# CEM-16bit-PCF8575.net
KiCad netlist of a schematic drawn in EAGLE
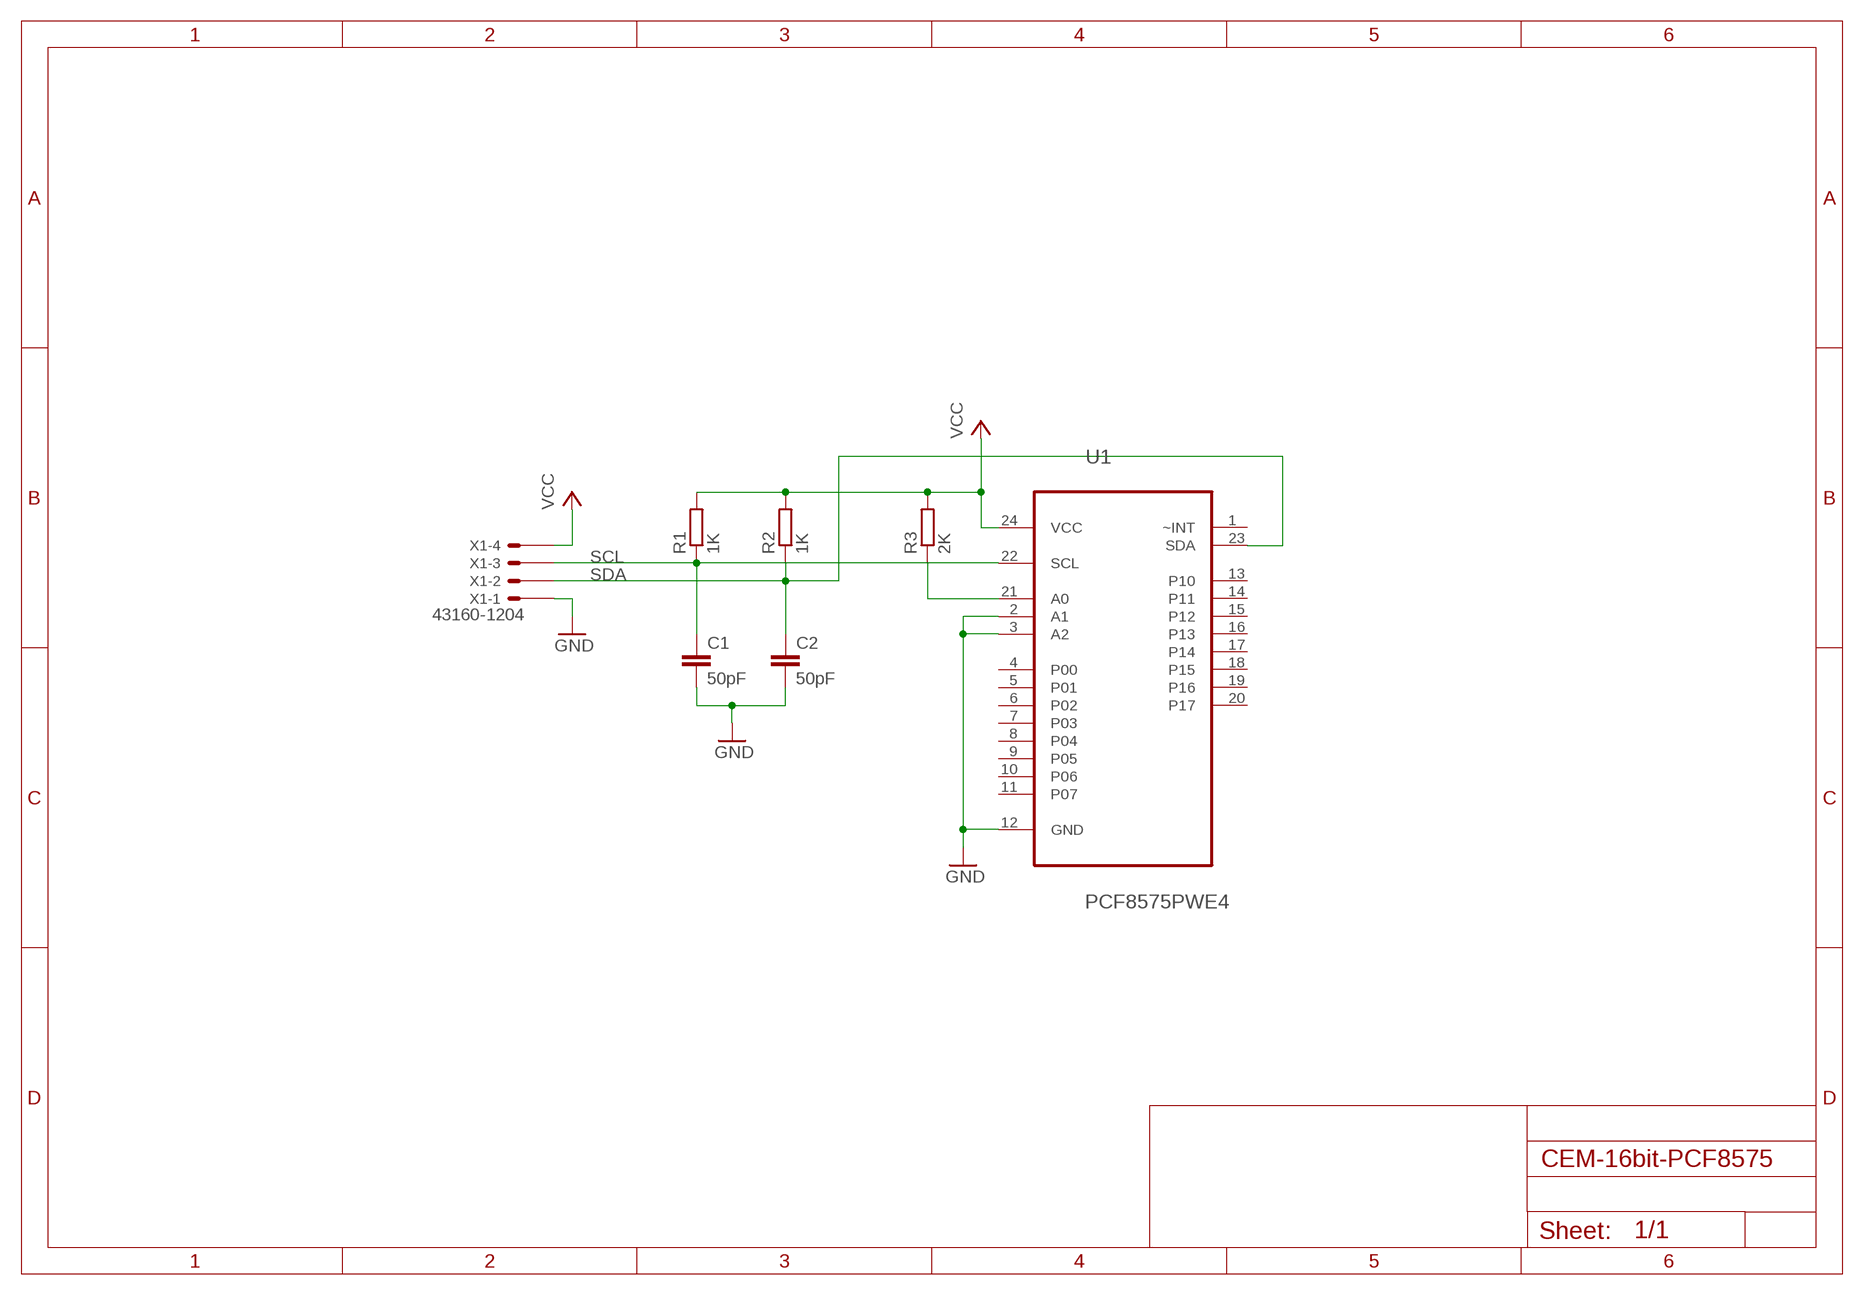
[diagram p0: schematic, sheet 1]

(export (version "E")
  (design (tool "Eeschema 10.0.6"))
  (components
    (comp (ref "C1")
      (value "50pF")
      (footprint "eagle-import:C1206K")
      (libsource (lib "eagle-import") (part "C-EUC1206K"))
    )
    (comp (ref "C2")
      (value "50pF")
      (footprint "eagle-import:C1206K")
      (libsource (lib "eagle-import") (part "C-EUC1206K"))
    )
    (comp (ref "R1")
      (value "1K")
      (footprint "eagle-import:M1406")
      (libsource (lib "eagle-import") (part "R-EU_M1406"))
    )
    (comp (ref "R2")
      (value "1K")
      (footprint "eagle-import:M1406")
      (libsource (lib "eagle-import") (part "R-EU_M1406"))
    )
    (comp (ref "R3")
      (value "2K")
      (footprint "eagle-import:M1406")
      (libsource (lib "eagle-import") (part "R-EU_M1406"))
    )
    (comp (ref "U1")
      (value "PCF8575PWE4")
      (footprint "eagle-import:SOP65P640X120-24N")
      (libsource (lib "eagle-import") (part "PCF8575PWE4"))
    )
    (comp (ref "X1")
      (value "43160-1204")
      (footprint "eagle-import:43160-XX04")
      (libsource (lib "eagle-import") (part "43160-0412"))
    )
  )
  (nets
    (net (code "1") (name "/SCL") (class "Default")
      (node (ref "C1") (pin "1") (pinfunction "1_1") (pintype "passive"))
      (node (ref "R1") (pin "1") (pinfunction "1_1") (pintype "passive"))
      (node (ref "U1") (pin "22") (pinfunction "SCL_22") (pintype "input"))
      (node (ref "X1") (pin "3@1") (pinfunction "S_3@1") (pintype "passive"))
    )
    (net (code "2") (name "/SDA") (class "Default")
      (node (ref "C2") (pin "1") (pinfunction "1_1") (pintype "passive"))
      (node (ref "R2") (pin "1") (pinfunction "1_1") (pintype "passive"))
      (node (ref "U1") (pin "23") (pinfunction "SDA_23") (pintype "bidirectional"))
      (node (ref "X1") (pin "2@1") (pinfunction "S_2@1") (pintype "passive"))
    )
    (net (code "3") (name "GND") (class "Default")
      (node (ref "C1") (pin "2") (pinfunction "2_2") (pintype "passive"))
      (node (ref "C2") (pin "2") (pinfunction "2_2") (pintype "passive"))
      (node (ref "U1") (pin "12") (pinfunction "GND_12") (pintype "passive"))
      (node (ref "U1") (pin "2") (pinfunction "A1_2") (pintype "input"))
      (node (ref "U1") (pin "3") (pinfunction "A2_3") (pintype "input"))
      (node (ref "X1") (pin "1@1") (pinfunction "S_1@1") (pintype "passive"))
    )
    (net (code "4") (name "Net-(U1-A0)") (class "Default")
      (node (ref "R3") (pin "1") (pinfunction "1_1") (pintype "passive"))
      (node (ref "U1") (pin "21") (pinfunction "A0_21") (pintype "input"))
    )
    (net (code "5") (name "VCC") (class "Default")
      (node (ref "R1") (pin "2") (pinfunction "2_2") (pintype "passive"))
      (node (ref "R2") (pin "2") (pinfunction "2_2") (pintype "passive"))
      (node (ref "R3") (pin "2") (pinfunction "2_2") (pintype "passive"))
      (node (ref "U1") (pin "24") (pinfunction "VCC_24") (pintype "power_in"))
      (node (ref "X1") (pin "4@1") (pinfunction "S_4@1") (pintype "passive"))
    )
    (net (code "6") (name "unconnected-(U1-P00-Pad4)") (class "Default")
      (node (ref "U1") (pin "4") (pinfunction "P00_4") (pintype "bidirectional"))
    )
    (net (code "7") (name "unconnected-(U1-P01-Pad5)") (class "Default")
      (node (ref "U1") (pin "5") (pinfunction "P01_5") (pintype "bidirectional"))
    )
    (net (code "8") (name "unconnected-(U1-P02-Pad6)") (class "Default")
      (node (ref "U1") (pin "6") (pinfunction "P02_6") (pintype "bidirectional"))
    )
    (net (code "9") (name "unconnected-(U1-P03-Pad7)") (class "Default")
      (node (ref "U1") (pin "7") (pinfunction "P03_7") (pintype "bidirectional"))
    )
    (net (code "10") (name "unconnected-(U1-P04-Pad8)") (class "Default")
      (node (ref "U1") (pin "8") (pinfunction "P04_8") (pintype "bidirectional"))
    )
    (net (code "11") (name "unconnected-(U1-P05-Pad9)") (class "Default")
      (node (ref "U1") (pin "9") (pinfunction "P05_9") (pintype "bidirectional"))
    )
    (net (code "12") (name "unconnected-(U1-P06-Pad10)") (class "Default")
      (node (ref "U1") (pin "10") (pinfunction "P06_10") (pintype "bidirectional"))
    )
    (net (code "13") (name "unconnected-(U1-P07-Pad11)") (class "Default")
      (node (ref "U1") (pin "11") (pinfunction "P07_11") (pintype "bidirectional"))
    )
    (net (code "14") (name "unconnected-(U1-P10-Pad13)") (class "Default")
      (node (ref "U1") (pin "13") (pinfunction "P10_13") (pintype "bidirectional"))
    )
    (net (code "15") (name "unconnected-(U1-P11-Pad14)") (class "Default")
      (node (ref "U1") (pin "14") (pinfunction "P11_14") (pintype "bidirectional"))
    )
    (net (code "16") (name "unconnected-(U1-P12-Pad15)") (class "Default")
      (node (ref "U1") (pin "15") (pinfunction "P12_15") (pintype "bidirectional"))
    )
    (net (code "17") (name "unconnected-(U1-P13-Pad16)") (class "Default")
      (node (ref "U1") (pin "16") (pinfunction "P13_16") (pintype "bidirectional"))
    )
    (net (code "18") (name "unconnected-(U1-P14-Pad17)") (class "Default")
      (node (ref "U1") (pin "17") (pinfunction "P14_17") (pintype "bidirectional"))
    )
    (net (code "19") (name "unconnected-(U1-P15-Pad18)") (class "Default")
      (node (ref "U1") (pin "18") (pinfunction "P15_18") (pintype "bidirectional"))
    )
    (net (code "20") (name "unconnected-(U1-P16-Pad19)") (class "Default")
      (node (ref "U1") (pin "19") (pinfunction "P16_19") (pintype "bidirectional"))
    )
    (net (code "21") (name "unconnected-(U1-P17-Pad20)") (class "Default")
      (node (ref "U1") (pin "20") (pinfunction "P17_20") (pintype "bidirectional"))
    )
    (net (code "22") (name "unconnected-(U1-~{INT}-Pad1)") (class "Default")
      (node (ref "U1") (pin "1") (pinfunction "~{INT}_1") (pintype "output"))
    )
    (net (code "23") (name "unconnected-(X1A-S-Pad1@2)") (class "Default")
      (node (ref "X1") (pin "1@2") (pinfunction "S_1@2") (pintype "passive"))
    )
    (net (code "24") (name "unconnected-(X1B-S-Pad2@2)") (class "Default")
      (node (ref "X1") (pin "2@2") (pinfunction "S_2@2") (pintype "passive"))
    )
    (net (code "25") (name "unconnected-(X1C-S-Pad3@2)") (class "Default")
      (node (ref "X1") (pin "3@2") (pinfunction "S_3@2") (pintype "passive"))
    )
    (net (code "26") (name "unconnected-(X1D-S-Pad4@2)") (class "Default")
      (node (ref "X1") (pin "4@2") (pinfunction "S_4@2") (pintype "passive"))
    )
  )
)
